# thewing_rev0_draft3.net
KiCad netlist of a schematic drawn in EAGLE
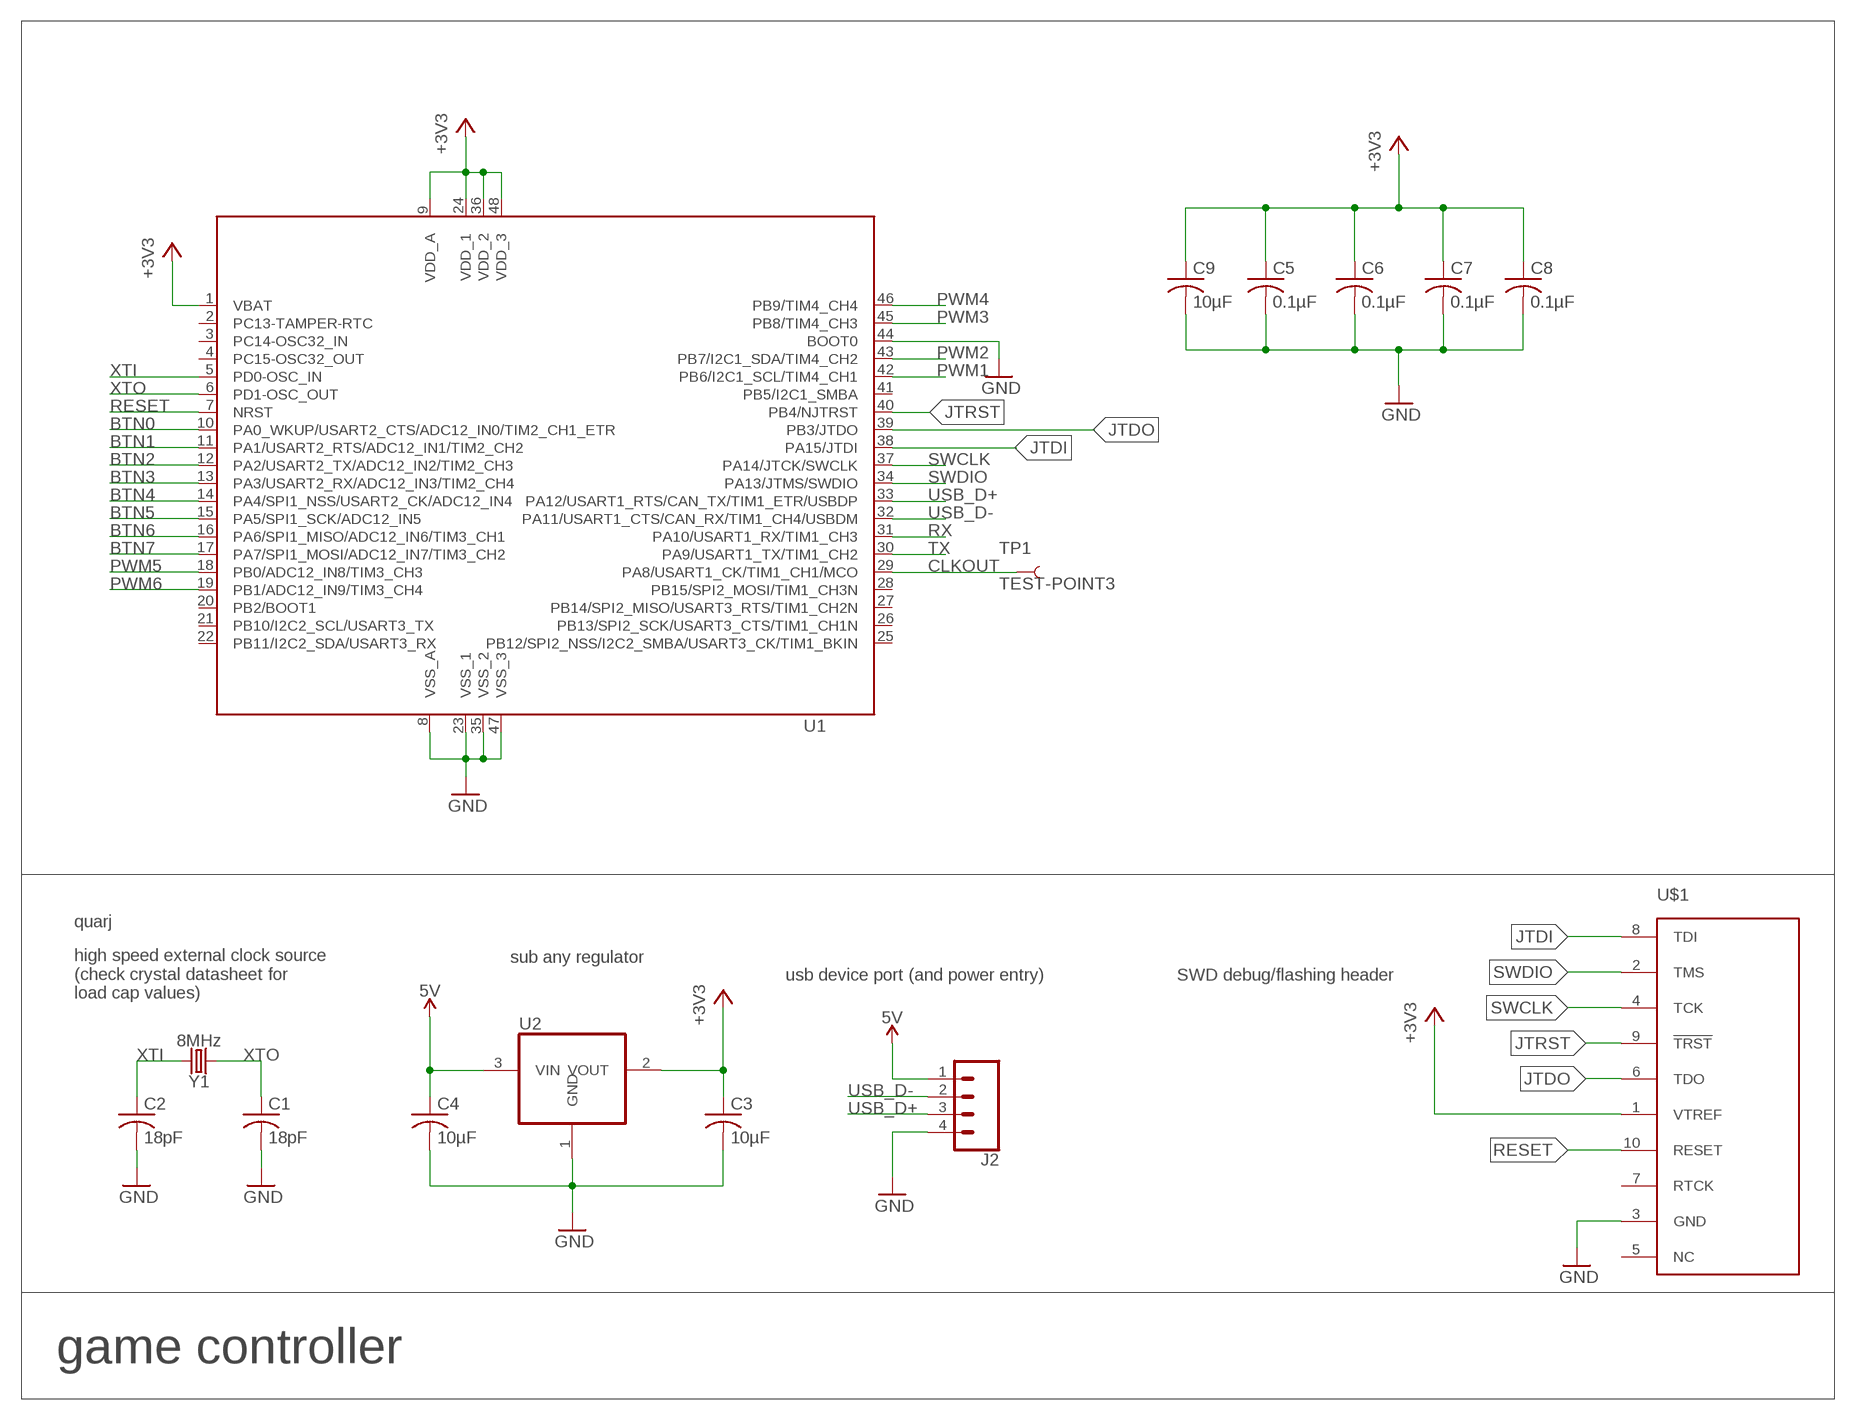
[diagram p0: schematic, sheet 1]
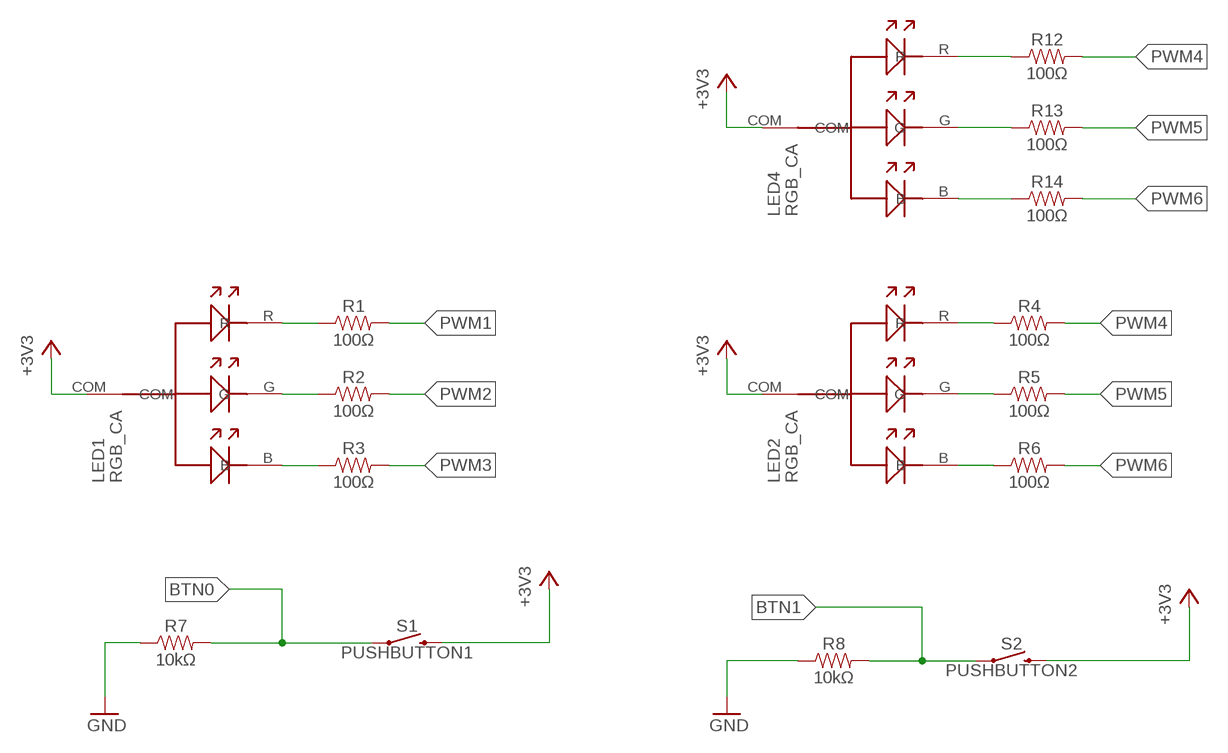
[diagram p1: schematic, sheet 2]
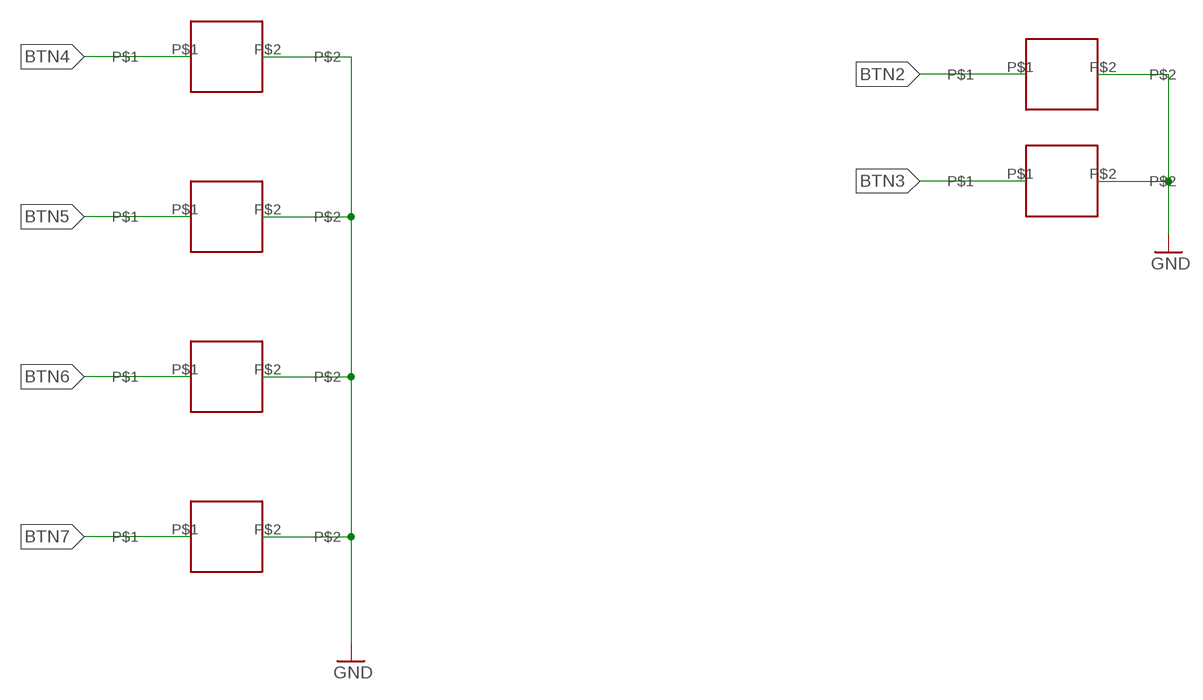
[diagram p2: schematic, sheet 3]

(export (version "E")
  (design (tool "Eeschema 10.0.6"))
  (components
    (comp (ref "C1")
      (value "18pF")
      (footprint "eagle-import:RCL_C0805K")
      (libsource (lib "eagle-import") (part "RCL_C-USC0805K"))
    )
    (comp (ref "C2")
      (value "18pF")
      (footprint "eagle-import:RCL_C0805K")
      (libsource (lib "eagle-import") (part "RCL_C-USC0805K"))
    )
    (comp (ref "C3")
      (value "10µF")
      (footprint "eagle-import:RCL_C0805K")
      (libsource (lib "eagle-import") (part "RCL_C-USC0805K"))
    )
    (comp (ref "C4")
      (value "10µF")
      (footprint "eagle-import:RCL_C0805K")
      (libsource (lib "eagle-import") (part "RCL_C-USC0805K"))
    )
    (comp (ref "C5")
      (value "0.1µF")
      (footprint "eagle-import:RCL_C0805K")
      (libsource (lib "eagle-import") (part "RCL_C-USC0805K"))
    )
    (comp (ref "C6")
      (value "0.1µF")
      (footprint "eagle-import:RCL_C0805K")
      (libsource (lib "eagle-import") (part "RCL_C-USC0805K"))
    )
    (comp (ref "C7")
      (value "0.1µF")
      (footprint "eagle-import:RCL_C0805K")
      (libsource (lib "eagle-import") (part "RCL_C-USC0805K"))
    )
    (comp (ref "C8")
      (value "0.1µF")
      (footprint "eagle-import:RCL_C0805K")
      (libsource (lib "eagle-import") (part "RCL_C-USC0805K"))
    )
    (comp (ref "C9")
      (value "10µF")
      (footprint "eagle-import:RCL_C0805K")
      (libsource (lib "eagle-import") (part "RCL_C-USC0805K"))
    )
    (comp (ref "J2")
      (value "CONN_04")
      (footprint "eagle-import:1X04")
      (libsource (lib "eagle-import") (part "CONN_04"))
    )
    (comp (ref "TP1")
      (value "TEST-POINT3")
      (footprint "eagle-import:PAD.03X.03")
      (libsource (lib "eagle-import") (part "TEST-POINT3"))
    )
    (comp (ref "U$1")
      (value "TC2050-NL-MCP-NL")
      (footprint "eagle-import:TC2030-MCP-NL")
      (libsource (lib "eagle-import") (part "TC2050-NL-MCP-NL"))
    )
    (comp (ref "U1")
      (value "STM32_STM32F102C4")
      (footprint "eagle-import:STM32_LQFP48")
      (libsource (lib "eagle-import") (part "STM32_STM32F102C4"))
    )
    (comp (ref "U2")
      (value "OG-VREG_REG1117")
      (footprint "eagle-import:OG-VREG_SOT223")
      (libsource (lib "eagle-import") (part "OG-VREG_REG1117"))
    )
    (comp (ref "Y1")
      (value "8MHz")
      (footprint "eagle-import:HC49UP")
      (libsource (lib "eagle-import") (part "CRYSTAL-8MHZSMD-HC49UP"))
    )
    (comp (ref "LED1")
      (value "RGB_CA")
      (footprint "eagle-import:RGB_LED_RECTANGULAR_COMMON_ANODE")
      (libsource (lib "eagle-import") (part "RGB_LED_RECTANGULAR_COMMON_ANODE"))
    )
    (comp (ref "LED2")
      (value "RGB_CA")
      (footprint "eagle-import:RGB_LED_RECTANGULAR_COMMON_ANODE")
      (libsource (lib "eagle-import") (part "RGB_LED_RECTANGULAR_COMMON_ANODE"))
    )
    (comp (ref "LED4")
      (value "RGB_CA")
      (footprint "eagle-import:RGB_LED_RECTANGULAR_COMMON_ANODE")
      (libsource (lib "eagle-import") (part "RGB_LED_RECTANGULAR_COMMON_ANODE"))
    )
    (comp (ref "R1")
      (value "100Ω")
      (footprint "eagle-import:0805")
      (libsource (lib "eagle-import") (part "0.3OHM-0805-1/8W-1%"))
    )
    (comp (ref "R2")
      (value "100Ω")
      (footprint "eagle-import:0805")
      (libsource (lib "eagle-import") (part "0.3OHM-0805-1/8W-1%"))
    )
    (comp (ref "R3")
      (value "100Ω")
      (footprint "eagle-import:0805")
      (libsource (lib "eagle-import") (part "0.3OHM-0805-1/8W-1%"))
    )
    (comp (ref "R4")
      (value "100Ω")
      (footprint "eagle-import:0805")
      (libsource (lib "eagle-import") (part "0.3OHM-0805-1/8W-1%"))
    )
    (comp (ref "R5")
      (value "100Ω")
      (footprint "eagle-import:0805")
      (libsource (lib "eagle-import") (part "0.3OHM-0805-1/8W-1%"))
    )
    (comp (ref "R6")
      (value "100Ω")
      (footprint "eagle-import:0805")
      (libsource (lib "eagle-import") (part "0.3OHM-0805-1/8W-1%"))
    )
    (comp (ref "R7")
      (value "10kΩ")
      (footprint "eagle-import:0805")
      (libsource (lib "eagle-import") (part "0.3OHM-0805-1/8W-1%"))
    )
    (comp (ref "R8")
      (value "10kΩ")
      (footprint "eagle-import:0805")
      (libsource (lib "eagle-import") (part "0.3OHM-0805-1/8W-1%"))
    )
    (comp (ref "R12")
      (value "100Ω")
      (footprint "eagle-import:0805")
      (libsource (lib "eagle-import") (part "0.3OHM-0805-1/8W-1%"))
    )
    (comp (ref "R13")
      (value "100Ω")
      (footprint "eagle-import:0805")
      (libsource (lib "eagle-import") (part "0.3OHM-0805-1/8W-1%"))
    )
    (comp (ref "R14")
      (value "100Ω")
      (footprint "eagle-import:0805")
      (libsource (lib "eagle-import") (part "0.3OHM-0805-1/8W-1%"))
    )
    (comp (ref "S1")
      (value "PUSHBUTTON1")
      (footprint "eagle-import:TACTILE_SWITCH_PTH_6.0MM")
      (libsource (lib "eagle-import") (part "MOMENTARY-SWITCH-SPST-PTH-6.0MM"))
    )
    (comp (ref "S2")
      (value "PUSHBUTTON2")
      (footprint "eagle-import:TACTILE_SWITCH_PTH_6.0MM")
      (libsource (lib "eagle-import") (part "MOMENTARY-SWITCH-SPST-PTH-6.0MM"))
    )
    (comp (ref "A")
      (value "HYPERKIN_TOUCHPAD_CADET")
      (footprint "eagle-import:HYPERKIN_TOUCHPLATE_CADET")
      (libsource (lib "eagle-import") (part "HYPERKIN_TOUCHPAD_CADET"))
    )
    (comp (ref "B")
      (value "HYPERKIN_TOUCHPAD_CADET")
      (footprint "eagle-import:HYPERKIN_TOUCHPLATE_CADET")
      (libsource (lib "eagle-import") (part "HYPERKIN_TOUCHPAD_CADET"))
    )
    (comp (ref "D")
      (value "HYPERKIN_TOUCHPAD_CADET")
      (footprint "eagle-import:HYPERKIN_TOUCHPLATE_CADET")
      (libsource (lib "eagle-import") (part "HYPERKIN_TOUCHPAD_CADET"))
    )
    (comp (ref "L")
      (value "HYPERKIN_TOUCHPAD_CADET")
      (footprint "eagle-import:HYPERKIN_TOUCHPLATE_CADET")
      (libsource (lib "eagle-import") (part "HYPERKIN_TOUCHPAD_CADET"))
    )
    (comp (ref "R")
      (value "HYPERKIN_TOUCHPAD_CADET")
      (footprint "eagle-import:HYPERKIN_TOUCHPLATE_CADET")
      (libsource (lib "eagle-import") (part "HYPERKIN_TOUCHPAD_CADET"))
    )
    (comp (ref "U")
      (value "HYPERKIN_TOUCHPAD_CADET")
      (footprint "eagle-import:HYPERKIN_TOUCHPLATE_CADET")
      (libsource (lib "eagle-import") (part "HYPERKIN_TOUCHPAD_CADET"))
    )
  )
  (nets
    (net (code "1") (name "+3V3") (class "Default")
      (node (ref "C3") (pin "1") (pinfunction "1_1") (pintype "passive"))
      (node (ref "C5") (pin "1") (pinfunction "1_1") (pintype "passive"))
      (node (ref "C6") (pin "1") (pinfunction "1_1") (pintype "passive"))
      (node (ref "C7") (pin "1") (pinfunction "1_1") (pintype "passive"))
      (node (ref "C8") (pin "1") (pinfunction "1_1") (pintype "passive"))
      (node (ref "C9") (pin "1") (pinfunction "1_1") (pintype "passive"))
      (node (ref "LED1") (pin "COM") (pinfunction "COM_COM") (pintype "bidirectional"))
      (node (ref "LED2") (pin "COM") (pinfunction "COM_COM") (pintype "bidirectional"))
      (node (ref "LED4") (pin "COM") (pinfunction "COM_COM") (pintype "bidirectional"))
      (node (ref "S1") (pin "3") (pinfunction "2_3") (pintype "passive"))
      (node (ref "S2") (pin "3") (pinfunction "2_3") (pintype "passive"))
      (node (ref "U$1") (pin "1") (pinfunction "VTREF_1") (pintype "bidirectional"))
      (node (ref "U1") (pin "1") (pinfunction "VBAT_1") (pintype "power_in"))
      (node (ref "U1") (pin "24") (pinfunction "VDD_1_24") (pintype "power_in"))
      (node (ref "U1") (pin "36") (pinfunction "VDD_2_36") (pintype "power_in"))
      (node (ref "U1") (pin "48") (pinfunction "VDD_3_48") (pintype "power_in"))
      (node (ref "U1") (pin "9") (pinfunction "VDD_A_9") (pintype "power_in"))
      (node (ref "U2") (pin "2") (pinfunction "VOUT_2") (pintype "output"))
    )
    (net (code "2") (name "5V") (class "Default")
      (node (ref "C4") (pin "1") (pinfunction "1_1") (pintype "passive"))
      (node (ref "J2") (pin "1") (pinfunction "1_1") (pintype "passive"))
      (node (ref "U2") (pin "3") (pinfunction "VIN_3") (pintype "input"))
    )
    (net (code "3") (name "BTN0") (class "Default")
      (node (ref "R7") (pin "2") (pinfunction "2_2") (pintype "passive"))
      (node (ref "S1") (pin "1") (pinfunction "1_1") (pintype "passive"))
      (node (ref "U1") (pin "10") (pinfunction "PA0_WKUP/USART2_CTS/ADC12_IN0/TIM2_CH1_ETR_10") (pintype "bidirectional"))
    )
    (net (code "4") (name "BTN1") (class "Default")
      (node (ref "R8") (pin "2") (pinfunction "2_2") (pintype "passive"))
      (node (ref "S2") (pin "1") (pinfunction "1_1") (pintype "passive"))
      (node (ref "U1") (pin "11") (pinfunction "PA1/USART2_RTS/ADC12_IN1/TIM2_CH2_11") (pintype "bidirectional"))
    )
    (net (code "5") (name "BTN2") (class "Default")
      (node (ref "A") (pin "P$1") (pinfunction "P$1_P$1") (pintype "bidirectional"))
      (node (ref "U1") (pin "12") (pinfunction "PA2/USART2_TX/ADC12_IN2/TIM2_CH3_12") (pintype "bidirectional"))
    )
    (net (code "6") (name "BTN3") (class "Default")
      (node (ref "B") (pin "P$1") (pinfunction "P$1_P$1") (pintype "bidirectional"))
      (node (ref "U1") (pin "13") (pinfunction "PA3/USART2_RX/ADC12_IN3/TIM2_CH4_13") (pintype "bidirectional"))
    )
    (net (code "7") (name "BTN4") (class "Default")
      (node (ref "U") (pin "P$1") (pinfunction "P$1_P$1") (pintype "bidirectional"))
      (node (ref "U1") (pin "14") (pinfunction "PA4/SPI1_NSS/USART2_CK/ADC12_IN4_14") (pintype "bidirectional"))
    )
    (net (code "8") (name "BTN5") (class "Default")
      (node (ref "D") (pin "P$1") (pinfunction "P$1_P$1") (pintype "bidirectional"))
      (node (ref "U1") (pin "15") (pinfunction "PA5/SPI1_SCK/ADC12_IN5_15") (pintype "bidirectional"))
    )
    (net (code "9") (name "BTN6") (class "Default")
      (node (ref "L") (pin "P$1") (pinfunction "P$1_P$1") (pintype "bidirectional"))
      (node (ref "U1") (pin "16") (pinfunction "PA6/SPI1_MISO/ADC12_IN6/TIM3_CH1_16") (pintype "bidirectional"))
    )
    (net (code "10") (name "BTN7") (class "Default")
      (node (ref "R") (pin "P$1") (pinfunction "P$1_P$1") (pintype "bidirectional"))
      (node (ref "U1") (pin "17") (pinfunction "PA7/SPI1_MOSI/ADC12_IN7/TIM3_CH2_17") (pintype "bidirectional"))
    )
    (net (code "11") (name "CLKOUT") (class "Default")
      (node (ref "TP1") (pin "P$1") (pinfunction "1_P$1") (pintype "bidirectional"))
      (node (ref "U1") (pin "29") (pinfunction "PA8/USART1_CK/TIM1_CH1/MCO_29") (pintype "bidirectional"))
    )
    (net (code "12") (name "GND") (class "Default")
      (node (ref "A") (pin "P$2") (pinfunction "P$2_P$2") (pintype "bidirectional"))
      (node (ref "B") (pin "P$2") (pinfunction "P$2_P$2") (pintype "bidirectional"))
      (node (ref "C1") (pin "2") (pinfunction "2_2") (pintype "passive"))
      (node (ref "C2") (pin "2") (pinfunction "2_2") (pintype "passive"))
      (node (ref "C3") (pin "2") (pinfunction "2_2") (pintype "passive"))
      (node (ref "C4") (pin "2") (pinfunction "2_2") (pintype "passive"))
      (node (ref "C5") (pin "2") (pinfunction "2_2") (pintype "passive"))
      (node (ref "C6") (pin "2") (pinfunction "2_2") (pintype "passive"))
      (node (ref "C7") (pin "2") (pinfunction "2_2") (pintype "passive"))
      (node (ref "C8") (pin "2") (pinfunction "2_2") (pintype "passive"))
      (node (ref "C9") (pin "2") (pinfunction "2_2") (pintype "passive"))
      (node (ref "D") (pin "P$2") (pinfunction "P$2_P$2") (pintype "bidirectional"))
      (node (ref "J2") (pin "4") (pinfunction "4_4") (pintype "passive"))
      (node (ref "L") (pin "P$2") (pinfunction "P$2_P$2") (pintype "bidirectional"))
      (node (ref "R") (pin "P$2") (pinfunction "P$2_P$2") (pintype "bidirectional"))
      (node (ref "R7") (pin "1") (pinfunction "1_1") (pintype "passive"))
      (node (ref "R8") (pin "1") (pinfunction "1_1") (pintype "passive"))
      (node (ref "U") (pin "P$2") (pinfunction "P$2_P$2") (pintype "bidirectional"))
      (node (ref "U$1") (pin "3") (pinfunction "GND_3") (pintype "bidirectional"))
      (node (ref "U1") (pin "23") (pinfunction "VSS_1_23") (pintype "power_in"))
      (node (ref "U1") (pin "35") (pinfunction "VSS_2_35") (pintype "power_in"))
      (node (ref "U1") (pin "44") (pinfunction "BOOT0_44") (pintype "input"))
      (node (ref "U1") (pin "47") (pinfunction "VSS_3_47") (pintype "power_in"))
      (node (ref "U1") (pin "8") (pinfunction "VSS_A_8") (pintype "power_in"))
      (node (ref "U2") (pin "1") (pinfunction "GND_1") (pintype "power_in"))
    )
    (net (code "13") (name "JTDI") (class "Default")
      (node (ref "U$1") (pin "8") (pinfunction "TDI_8") (pintype "bidirectional"))
      (node (ref "U1") (pin "38") (pinfunction "PA15/JTDI_38") (pintype "bidirectional"))
    )
    (net (code "14") (name "JTDO") (class "Default")
      (node (ref "U$1") (pin "6") (pinfunction "TDO_6") (pintype "bidirectional"))
      (node (ref "U1") (pin "39") (pinfunction "PB3/JTDO_39") (pintype "bidirectional"))
    )
    (net (code "15") (name "JTRST") (class "Default")
      (node (ref "U$1") (pin "9") (pinfunction "~{TRST}_9") (pintype "bidirectional"))
      (node (ref "U1") (pin "40") (pinfunction "PB4/NJTRST_40") (pintype "bidirectional"))
    )
    (net (code "16") (name "Net-(LED1-PadB)") (class "Default")
      (node (ref "LED1") (pin "B") (pinfunction "B_B") (pintype "bidirectional"))
      (node (ref "R3") (pin "1") (pinfunction "1_1") (pintype "passive"))
    )
    (net (code "17") (name "Net-(LED1-PadG)") (class "Default")
      (node (ref "LED1") (pin "G") (pinfunction "G_G") (pintype "bidirectional"))
      (node (ref "R2") (pin "1") (pinfunction "1_1") (pintype "passive"))
    )
    (net (code "18") (name "Net-(LED1-PadR)") (class "Default")
      (node (ref "LED1") (pin "R") (pinfunction "R_R") (pintype "bidirectional"))
      (node (ref "R1") (pin "1") (pinfunction "1_1") (pintype "passive"))
    )
    (net (code "19") (name "Net-(LED2-PadB)") (class "Default")
      (node (ref "LED2") (pin "B") (pinfunction "B_B") (pintype "bidirectional"))
      (node (ref "R6") (pin "1") (pinfunction "1_1") (pintype "passive"))
    )
    (net (code "20") (name "Net-(LED2-PadG)") (class "Default")
      (node (ref "LED2") (pin "G") (pinfunction "G_G") (pintype "bidirectional"))
      (node (ref "R5") (pin "1") (pinfunction "1_1") (pintype "passive"))
    )
    (net (code "21") (name "Net-(LED2-PadR)") (class "Default")
      (node (ref "LED2") (pin "R") (pinfunction "R_R") (pintype "bidirectional"))
      (node (ref "R4") (pin "1") (pinfunction "1_1") (pintype "passive"))
    )
    (net (code "22") (name "Net-(LED4-PadB)") (class "Default")
      (node (ref "LED4") (pin "B") (pinfunction "B_B") (pintype "bidirectional"))
      (node (ref "R14") (pin "1") (pinfunction "1_1") (pintype "passive"))
    )
    (net (code "23") (name "Net-(LED4-PadG)") (class "Default")
      (node (ref "LED4") (pin "G") (pinfunction "G_G") (pintype "bidirectional"))
      (node (ref "R13") (pin "1") (pinfunction "1_1") (pintype "passive"))
    )
    (net (code "24") (name "Net-(LED4-PadR)") (class "Default")
      (node (ref "LED4") (pin "R") (pinfunction "R_R") (pintype "bidirectional"))
      (node (ref "R12") (pin "1") (pinfunction "1_1") (pintype "passive"))
    )
    (net (code "25") (name "PWM1") (class "Default")
      (node (ref "R1") (pin "2") (pinfunction "2_2") (pintype "passive"))
      (node (ref "U1") (pin "42") (pinfunction "PB6/I2C1_SCL/TIM4_CH1_42") (pintype "input"))
    )
    (net (code "26") (name "PWM2") (class "Default")
      (node (ref "R2") (pin "2") (pinfunction "2_2") (pintype "passive"))
      (node (ref "U1") (pin "43") (pinfunction "PB7/I2C1_SDA/TIM4_CH2_43") (pintype "bidirectional"))
    )
    (net (code "27") (name "PWM3") (class "Default")
      (node (ref "R3") (pin "2") (pinfunction "2_2") (pintype "passive"))
      (node (ref "U1") (pin "45") (pinfunction "PB8/TIM4_CH3_45") (pintype "bidirectional"))
    )
    (net (code "28") (name "PWM4") (class "Default")
      (node (ref "R12") (pin "2") (pinfunction "2_2") (pintype "passive"))
      (node (ref "R4") (pin "2") (pinfunction "2_2") (pintype "passive"))
      (node (ref "U1") (pin "46") (pinfunction "PB9/TIM4_CH4_46") (pintype "input"))
    )
    (net (code "29") (name "PWM5") (class "Default")
      (node (ref "R13") (pin "2") (pinfunction "2_2") (pintype "passive"))
      (node (ref "R5") (pin "2") (pinfunction "2_2") (pintype "passive"))
      (node (ref "U1") (pin "18") (pinfunction "PB0/ADC12_IN8/TIM3_CH3_18") (pintype "bidirectional"))
    )
    (net (code "30") (name "PWM6") (class "Default")
      (node (ref "R14") (pin "2") (pinfunction "2_2") (pintype "passive"))
      (node (ref "R6") (pin "2") (pinfunction "2_2") (pintype "passive"))
      (node (ref "U1") (pin "19") (pinfunction "PB1/ADC12_IN9/TIM3_CH4_19") (pintype "bidirectional"))
    )
    (net (code "31") (name "RESET") (class "Default")
      (node (ref "U$1") (pin "10") (pinfunction "RESET_10") (pintype "bidirectional"))
      (node (ref "U1") (pin "7") (pinfunction "NRST_7") (pintype "input"))
    )
    (net (code "32") (name "RX") (class "Default")
      (node (ref "U1") (pin "31") (pinfunction "PA10/USART1_RX/TIM1_CH3_31") (pintype "bidirectional"))
    )
    (net (code "33") (name "SWCLK") (class "Default")
      (node (ref "U$1") (pin "4") (pinfunction "TCK_4") (pintype "bidirectional"))
      (node (ref "U1") (pin "37") (pinfunction "PA14/JTCK/SWCLK_37") (pintype "bidirectional"))
    )
    (net (code "34") (name "SWDIO") (class "Default")
      (node (ref "U$1") (pin "2") (pinfunction "TMS_2") (pintype "bidirectional"))
      (node (ref "U1") (pin "34") (pinfunction "PA13/JTMS/SWDIO_34") (pintype "bidirectional"))
    )
    (net (code "35") (name "TX") (class "Default")
      (node (ref "U1") (pin "30") (pinfunction "PA9/USART1_TX/TIM1_CH2_30") (pintype "input"))
    )
    (net (code "36") (name "USB_D+") (class "Default")
      (node (ref "J2") (pin "3") (pinfunction "3_3") (pintype "passive"))
      (node (ref "U1") (pin "33") (pinfunction "PA12/USART1_RTS/CAN_TX/TIM1_ETR/USBDP_33") (pintype "bidirectional"))
    )
    (net (code "37") (name "USB_D-") (class "Default")
      (node (ref "J2") (pin "2") (pinfunction "2_2") (pintype "passive"))
      (node (ref "U1") (pin "32") (pinfunction "PA11/USART1_CTS/CAN_RX/TIM1_CH4/USBDM_32") (pintype "bidirectional"))
    )
    (net (code "38") (name "XTI") (class "Default")
      (node (ref "C2") (pin "1") (pinfunction "1_1") (pintype "passive"))
      (node (ref "U1") (pin "5") (pinfunction "PD0-OSC_IN_5") (pintype "input"))
      (node (ref "Y1") (pin "2") (pinfunction "2_2") (pintype "passive"))
    )
    (net (code "39") (name "XTO") (class "Default")
      (node (ref "C1") (pin "1") (pinfunction "1_1") (pintype "passive"))
      (node (ref "U1") (pin "6") (pinfunction "PD1-OSC_OUT_6") (pintype "input"))
      (node (ref "Y1") (pin "1") (pinfunction "1_1") (pintype "passive"))
    )
    (net (code "40") (name "unconnected-(U$1-NC-Pad5)") (class "Default")
      (node (ref "U$1") (pin "5") (pinfunction "NC_5") (pintype "bidirectional"))
    )
    (net (code "41") (name "unconnected-(U$1-RTCK-Pad7)") (class "Default")
      (node (ref "U$1") (pin "7") (pinfunction "RTCK_7") (pintype "bidirectional"))
    )
    (net (code "42") (name "unconnected-(U1-PB2{slash}BOOT1-Pad20)") (class "Default")
      (node (ref "U1") (pin "20") (pinfunction "PB2/BOOT1_20") (pintype "bidirectional"))
    )
    (net (code "43") (name "unconnected-(U1-PB5{slash}I2C1_SMBA-Pad41)") (class "Default")
      (node (ref "U1") (pin "41") (pinfunction "PB5/I2C1_SMBA_41") (pintype "input"))
    )
    (net (code "44") (name "unconnected-(U1-PB10{slash}I2C2_SCL{slash}USART3_TX-Pad21)") (class "Default")
      (node (ref "U1") (pin "21") (pinfunction "PB10/I2C2_SCL/USART3_TX_21") (pintype "input"))
    )
    (net (code "45") (name "unconnected-(U1-PB11{slash}I2C2_SDA{slash}USART3_RX-Pad22)") (class "Default")
      (node (ref "U1") (pin "22") (pinfunction "PB11/I2C2_SDA/USART3_RX_22") (pintype "input"))
    )
    (net (code "46") (name "unconnected-(U1-PB12{slash}SPI2_NSS{slash}I2C2_SMBA{slash}USART3_CK{slash}TIM1_BKIN-Pad25)") (class "Default")
      (node (ref "U1") (pin "25") (pinfunction "PB12/SPI2_NSS/I2C2_SMBA/USART3_CK/TIM1_BKIN_25") (pintype "input"))
    )
    (net (code "47") (name "unconnected-(U1-PB13{slash}SPI2_SCK{slash}USART3_CTS{slash}TIM1_CH1N-Pad26)") (class "Default")
      (node (ref "U1") (pin "26") (pinfunction "PB13/SPI2_SCK/USART3_CTS/TIM1_CH1N_26") (pintype "input"))
    )
    (net (code "48") (name "unconnected-(U1-PB14{slash}SPI2_MISO{slash}USART3_RTS{slash}TIM1_CH2N-Pad27)") (class "Default")
      (node (ref "U1") (pin "27") (pinfunction "PB14/SPI2_MISO/USART3_RTS/TIM1_CH2N_27") (pintype "input"))
    )
    (net (code "49") (name "unconnected-(U1-PB15{slash}SPI2_MOSI{slash}TIM1_CH3N-Pad28)") (class "Default")
      (node (ref "U1") (pin "28") (pinfunction "PB15/SPI2_MOSI/TIM1_CH3N_28") (pintype "input"))
    )
    (net (code "50") (name "unconnected-(U1-PC13-TAMPER-RTC-Pad2)") (class "Default")
      (node (ref "U1") (pin "2") (pinfunction "PC13-TAMPER-RTC_2") (pintype "input"))
    )
    (net (code "51") (name "unconnected-(U1-PC14-OSC32_IN-Pad3)") (class "Default")
      (node (ref "U1") (pin "3") (pinfunction "PC14-OSC32_IN_3") (pintype "input"))
    )
    (net (code "52") (name "unconnected-(U1-PC15-OSC32_OUT-Pad4)") (class "Default")
      (node (ref "U1") (pin "4") (pinfunction "PC15-OSC32_OUT_4") (pintype "input"))
    )
  )
)
